# Light_Gates.net
KiCad netlist of a schematic drawn in Altium Designer
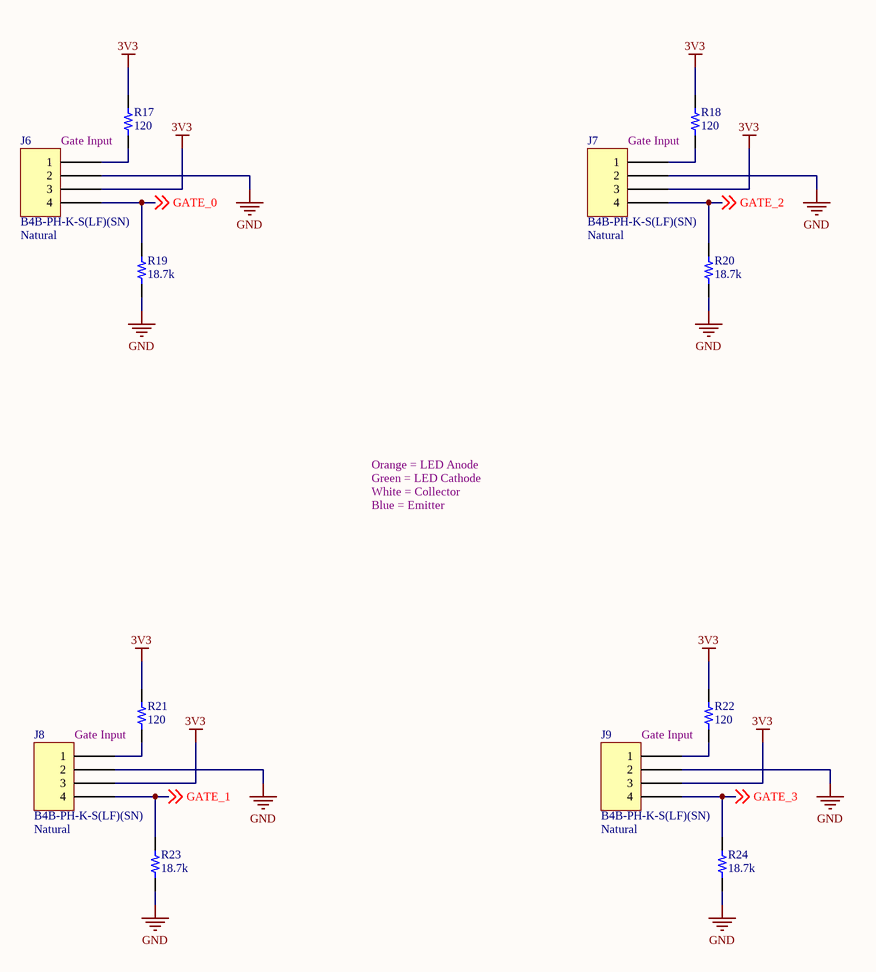
[diagram p0: Light Gates.SchDoc]

(export (version "E")
  (design (tool "Eeschema 10.0.6"))
  (components
    (comp (ref "J6")
      (value "B4B-PH-K-S(LF)(SN)")
      (footprint "JST B4B-PH-K")
      (description "CONN HEADER PH TOP 4POS 2MM")
      (fields (field (name "COLOUR") "Natural") (field (name "MANUFACTURER") "JST Sales America Inc."))
      (libsource (lib "Celestial Library Database") (part "4 Pin"))
    )
    (comp (ref "J7")
      (value "B4B-PH-K-S(LF)(SN)")
      (footprint "JST B4B-PH-K")
      (description "CONN HEADER PH TOP 4POS 2MM")
      (fields (field (name "COLOUR") "Natural") (field (name "MANUFACTURER") "JST Sales America Inc."))
      (libsource (lib "Celestial Library Database") (part "4 Pin"))
    )
    (comp (ref "J8")
      (value "B4B-PH-K-S(LF)(SN)")
      (footprint "JST B4B-PH-K")
      (description "CONN HEADER PH TOP 4POS 2MM")
      (fields (field (name "COLOUR") "Natural") (field (name "MANUFACTURER") "JST Sales America Inc."))
      (libsource (lib "Celestial Library Database") (part "4 Pin"))
    )
    (comp (ref "J9")
      (value "B4B-PH-K-S(LF)(SN)")
      (footprint "JST B4B-PH-K")
      (description "CONN HEADER PH TOP 4POS 2MM")
      (fields (field (name "COLOUR") "Natural") (field (name "MANUFACTURER") "JST Sales America Inc."))
      (libsource (lib "Celestial Library Database") (part "4 Pin"))
    )
    (comp (ref "R17")
      (value "120")
      (footprint "RES 0603/1608")
      (description "RES SMD 120 OHM 1% 1/10W 0603")
      (fields
        (field (name "PART NUMBER") "ERJ-3EKF1200V")
        (field (name "MANUFACTURER") "Panasonic Electronic Components")
      )
      (libsource (lib "Celestial Library Database") (part "Resistor"))
    )
    (comp (ref "R18")
      (value "120")
      (footprint "RES 0603/1608")
      (description "RES SMD 120 OHM 1% 1/10W 0603")
      (fields
        (field (name "PART NUMBER") "ERJ-3EKF1200V")
        (field (name "MANUFACTURER") "Panasonic Electronic Components")
      )
      (libsource (lib "Celestial Library Database") (part "Resistor"))
    )
    (comp (ref "R19")
      (value "18.7k")
      (footprint "RES 0603/1608")
      (description "RES SMD 18.7K OHM 1% 1/10W 0603")
      (fields
        (field (name "PART NUMBER") "ERJ-3EKF1872V")
        (field (name "MANUFACTURER") "Panasonic Electronic Components")
      )
      (libsource (lib "Celestial Library Database") (part "Resistor"))
    )
    (comp (ref "R20")
      (value "18.7k")
      (footprint "RES 0603/1608")
      (description "RES SMD 18.7K OHM 1% 1/10W 0603")
      (fields
        (field (name "PART NUMBER") "ERJ-3EKF1872V")
        (field (name "MANUFACTURER") "Panasonic Electronic Components")
      )
      (libsource (lib "Celestial Library Database") (part "Resistor"))
    )
    (comp (ref "R21")
      (value "120")
      (footprint "RES 0603/1608")
      (description "RES SMD 120 OHM 1% 1/10W 0603")
      (fields
        (field (name "PART NUMBER") "ERJ-3EKF1200V")
        (field (name "MANUFACTURER") "Panasonic Electronic Components")
      )
      (libsource (lib "Celestial Library Database") (part "Resistor"))
    )
    (comp (ref "R22")
      (value "120")
      (footprint "RES 0603/1608")
      (description "RES SMD 120 OHM 1% 1/10W 0603")
      (fields
        (field (name "PART NUMBER") "ERJ-3EKF1200V")
        (field (name "MANUFACTURER") "Panasonic Electronic Components")
      )
      (libsource (lib "Celestial Library Database") (part "Resistor"))
    )
    (comp (ref "R23")
      (value "18.7k")
      (footprint "RES 0603/1608")
      (description "RES SMD 18.7K OHM 1% 1/10W 0603")
      (fields
        (field (name "PART NUMBER") "ERJ-3EKF1872V")
        (field (name "MANUFACTURER") "Panasonic Electronic Components")
      )
      (libsource (lib "Celestial Library Database") (part "Resistor"))
    )
    (comp (ref "R24")
      (value "18.7k")
      (footprint "RES 0603/1608")
      (description "RES SMD 18.7K OHM 1% 1/10W 0603")
      (fields
        (field (name "PART NUMBER") "ERJ-3EKF1872V")
        (field (name "MANUFACTURER") "Panasonic Electronic Components")
      )
      (libsource (lib "Celestial Library Database") (part "Resistor"))
    )
  )
  (nets
    (net (code "1") (name "3V3") (class "Default")
      (node (ref "J6") (pin "3") (pinfunction "3_3") (pintype "passive"))
      (node (ref "J7") (pin "3") (pinfunction "3_3") (pintype "passive"))
      (node (ref "J8") (pin "3") (pinfunction "3_3") (pintype "passive"))
      (node (ref "J9") (pin "3") (pinfunction "3_3") (pintype "passive"))
      (node (ref "R17") (pin "2") (pinfunction "2_2") (pintype "passive"))
      (node (ref "R18") (pin "2") (pinfunction "2_2") (pintype "passive"))
      (node (ref "R21") (pin "2") (pinfunction "2_2") (pintype "passive"))
      (node (ref "R22") (pin "2") (pinfunction "2_2") (pintype "passive"))
    )
    (net (code "2") (name "GATE_0") (class "Default")
      (node (ref "J6") (pin "4") (pinfunction "4_4") (pintype "passive"))
      (node (ref "R19") (pin "2") (pinfunction "2_2") (pintype "passive"))
    )
    (net (code "3") (name "GATE_1") (class "Default")
      (node (ref "J8") (pin "4") (pinfunction "4_4") (pintype "passive"))
      (node (ref "R23") (pin "2") (pinfunction "2_2") (pintype "passive"))
    )
    (net (code "4") (name "GATE_2") (class "Default")
      (node (ref "J7") (pin "4") (pinfunction "4_4") (pintype "passive"))
      (node (ref "R20") (pin "2") (pinfunction "2_2") (pintype "passive"))
    )
    (net (code "5") (name "GATE_3") (class "Default")
      (node (ref "J9") (pin "4") (pinfunction "4_4") (pintype "passive"))
      (node (ref "R24") (pin "2") (pinfunction "2_2") (pintype "passive"))
    )
    (net (code "6") (name "GND") (class "Default")
      (node (ref "J6") (pin "2") (pinfunction "2_2") (pintype "passive"))
      (node (ref "J7") (pin "2") (pinfunction "2_2") (pintype "passive"))
      (node (ref "J8") (pin "2") (pinfunction "2_2") (pintype "passive"))
      (node (ref "J9") (pin "2") (pinfunction "2_2") (pintype "passive"))
      (node (ref "R19") (pin "1") (pinfunction "1_1") (pintype "passive"))
      (node (ref "R20") (pin "1") (pinfunction "1_1") (pintype "passive"))
      (node (ref "R23") (pin "1") (pinfunction "1_1") (pintype "passive"))
      (node (ref "R24") (pin "1") (pinfunction "1_1") (pintype "passive"))
    )
    (net (code "7") (name "Net-(J6-Pad1)") (class "Default")
      (node (ref "J6") (pin "1") (pinfunction "1_1") (pintype "passive"))
      (node (ref "R17") (pin "1") (pinfunction "1_1") (pintype "passive"))
    )
    (net (code "8") (name "Net-(J7-Pad1)") (class "Default")
      (node (ref "J7") (pin "1") (pinfunction "1_1") (pintype "passive"))
      (node (ref "R18") (pin "1") (pinfunction "1_1") (pintype "passive"))
    )
    (net (code "9") (name "Net-(J8-Pad1)") (class "Default")
      (node (ref "J8") (pin "1") (pinfunction "1_1") (pintype "passive"))
      (node (ref "R21") (pin "1") (pinfunction "1_1") (pintype "passive"))
    )
    (net (code "10") (name "Net-(J9-Pad1)") (class "Default")
      (node (ref "J9") (pin "1") (pinfunction "1_1") (pintype "passive"))
      (node (ref "R22") (pin "1") (pinfunction "1_1") (pintype "passive"))
    )
  )
)
